# USB.net
KiCad netlist of a schematic drawn in Altium Designer
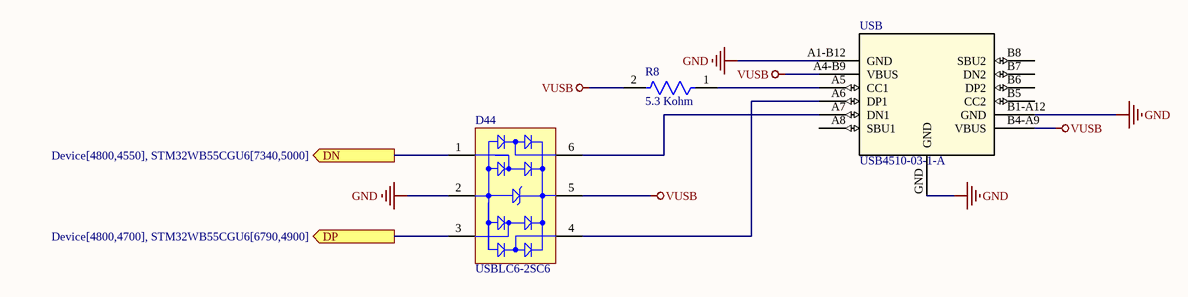
[diagram p0: USB.SchDoc]

(export (version "E")
  (design (tool "Eeschema 10.0.6"))
  (components
    (comp (ref "D44")
      (value "USBLC6-2SC6")
      (footprint "STM-SOT23-6L_V")
      (description "Very low capacitance ESD protection, 3.5 pF, -40 to 125 degC, 6-Pin SOT23, RoHS, Tape and Reel")
      (fields (field (name "MANUFACTURER") "STMicroelectronics"))
      (libsource (lib "Altium Content Vault") (part "STM-USB_DVI_HDMIULC6-4SC6X-SOT23-6L"))
    )
    (comp (ref "R8")
      (value "5.3 Kohm")
      (footprint "FP-RC1005-IPC_C")
      (description "Res Thick Film 0402 1.87kΩ 1% 0.063W ±100ppm/°C Molded SMD T/R")
      (fields (field (name "TOLERANCE") "1%"))
      (libsource (lib "Altium Content Vault") (part "1029c3af85768c4190bb7ad29bc67b5"))
    )
    (comp (ref "USB")
      (value "USB4510-03-1-A")
      (footprint "USB4510-03-1-A")
      (libsource (lib "ReadyButNotListed") (part "USB4510-03-1-A"))
    )
  )
  (nets
    (net (code "1") (name "/DN") (class "Default")
      (node (ref "D44") (pin "1") (pinfunction "I/O_1_1") (pintype "passive"))
    )
    (net (code "2") (name "/DP") (class "Default")
      (node (ref "D44") (pin "3") (pinfunction "I/O_2_3") (pintype "passive"))
    )
    (net (code "3") (name "GND") (class "Default")
      (node (ref "D44") (pin "2") (pinfunction "GND_2") (pintype "passive"))
      (node (ref "USB") (pin "A1-B12") (pinfunction "GND_A1-B12") (pintype "passive"))
      (node (ref "USB") (pin "B1-A12") (pinfunction "GND_B1-A12") (pintype "passive"))
      (node (ref "USB") (pin "GND") (pinfunction "GND_GND") (pintype "passive"))
    )
    (net (code "4") (name "Net-(D44-I{slash}O_3)") (class "Default")
      (node (ref "D44") (pin "4") (pinfunction "I/O_3_4") (pintype "passive"))
      (node (ref "USB") (pin "A6") (pinfunction "DP1_A6") (pintype "bidirectional"))
    )
    (net (code "5") (name "Net-(D44-I{slash}O_4)") (class "Default")
      (node (ref "D44") (pin "6") (pinfunction "I/O_4_6") (pintype "passive"))
      (node (ref "USB") (pin "A7") (pinfunction "DN1_A7") (pintype "bidirectional"))
    )
    (net (code "6") (name "Net-(USB-CC1)") (class "Default")
      (node (ref "R8") (pin "1") (pinfunction "1_1") (pintype "passive"))
      (node (ref "USB") (pin "A5") (pinfunction "CC1_A5") (pintype "bidirectional"))
    )
    (net (code "7") (name "VUSB") (class "Default")
      (node (ref "D44") (pin "5") (pinfunction "VBUS_5") (pintype "passive"))
      (node (ref "R8") (pin "2") (pinfunction "2_2") (pintype "passive"))
      (node (ref "USB") (pin "A4-B9") (pinfunction "VBUS_A4-B9") (pintype "power_in"))
      (node (ref "USB") (pin "B4-A9") (pinfunction "VBUS_B4-A9") (pintype "power_in"))
    )
    (net (code "8") (name "unconnected-(USB-CC2-PadB5)") (class "Default")
      (node (ref "USB") (pin "B5") (pinfunction "CC2_B5") (pintype "bidirectional"))
    )
    (net (code "9") (name "unconnected-(USB-DN2-PadB7)") (class "Default")
      (node (ref "USB") (pin "B7") (pinfunction "DN2_B7") (pintype "bidirectional"))
    )
    (net (code "10") (name "unconnected-(USB-DP2-PadB6)") (class "Default")
      (node (ref "USB") (pin "B6") (pinfunction "DP2_B6") (pintype "bidirectional"))
    )
    (net (code "11") (name "unconnected-(USB-SBU1-PadA8)") (class "Default")
      (node (ref "USB") (pin "A8") (pinfunction "SBU1_A8") (pintype "bidirectional"))
    )
    (net (code "12") (name "unconnected-(USB-SBU2-PadB8)") (class "Default")
      (node (ref "USB") (pin "B8") (pinfunction "SBU2_B8") (pintype "bidirectional"))
    )
  )
)
